# ArticulatedPCBEndLED.net
KiCad netlist of a schematic drawn in EAGLE
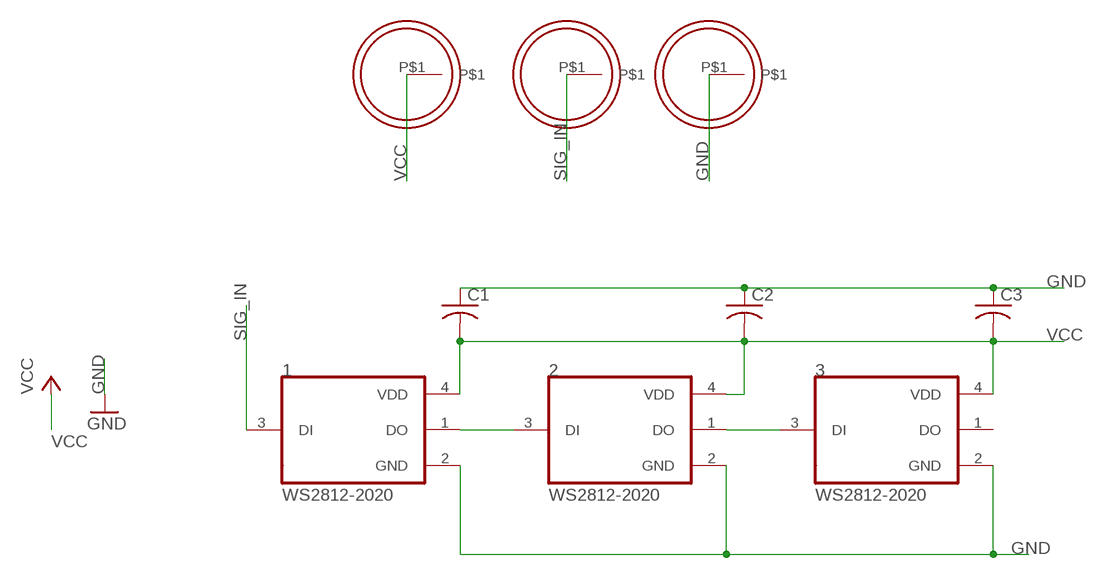
[diagram p0: schematic, sheet 1]

(export (version "E")
  (design (tool "Eeschema 10.0.6"))
  (components
    (comp (ref "1")
      (value "WS2812-2020")
      (footprint "eagle-import:LED_WS2812-2020")
      (fields (field (name "MF") "Worldsemi"))
      (libsource (lib "eagle-import") (part "WS2812-2020"))
    )
    (comp (ref "2")
      (value "WS2812-2020")
      (footprint "eagle-import:LED_WS2812-2020")
      (fields (field (name "MF") "Worldsemi"))
      (libsource (lib "eagle-import") (part "WS2812-2020"))
    )
    (comp (ref "3")
      (value "WS2812-2020")
      (footprint "eagle-import:LED_WS2812-2020")
      (fields (field (name "MF") "Worldsemi"))
      (libsource (lib "eagle-import") (part "WS2812-2020"))
    )
    (comp (ref "C1")
      (value "C-USC0603")
      (footprint "eagle-import:C0603")
      (libsource (lib "eagle-import") (part "C-USC0603"))
    )
    (comp (ref "C2")
      (value "C-USC0603")
      (footprint "eagle-import:C0603")
      (libsource (lib "eagle-import") (part "C-USC0603"))
    )
    (comp (ref "C3")
      (value "C-USC0603")
      (footprint "eagle-import:C0603")
      (libsource (lib "eagle-import") (part "C-USC0603"))
    )
    (comp (ref "U$2")
      (value "CIRCLE_PAD_17_2_OD")
      (footprint "eagle-import:CIRCLE_PAD_17_2_OD")
      (libsource (lib "eagle-import") (part "CIRCLE_PAD_17_2_OD"))
    )
    (comp (ref "U$3")
      (value "CIRCLE_PAD_8_2_OD")
      (footprint "eagle-import:CIRCLE_PAD_8_2_OD")
      (libsource (lib "eagle-import") (part "CIRCLE_PAD_8_2_OD"))
    )
    (comp (ref "U$4")
      (value "CIRCLE_PAD_12_7_OD")
      (footprint "eagle-import:CIRCLE_PAD_12_7_OD")
      (libsource (lib "eagle-import") (part "CIRCLE_PAD_12_7_OD"))
    )
  )
  (nets
    (net (code "1") (name "/SIG_IN") (class "Default")
      (node (ref "1") (pin "3") (pinfunction "DI_3") (pintype "input"))
      (node (ref "U$4") (pin "P$1") (pinfunction "P$1_P$1") (pintype "bidirectional"))
    )
    (net (code "2") (name "GND") (class "Default")
      (node (ref "1") (pin "2") (pinfunction "GND_2") (pintype "power_in"))
      (node (ref "2") (pin "2") (pinfunction "GND_2") (pintype "power_in"))
      (node (ref "3") (pin "2") (pinfunction "GND_2") (pintype "power_in"))
      (node (ref "C1") (pin "1") (pinfunction "1_1") (pintype "passive"))
      (node (ref "C2") (pin "1") (pinfunction "1_1") (pintype "passive"))
      (node (ref "C3") (pin "1") (pinfunction "1_1") (pintype "passive"))
      (node (ref "U$2") (pin "P$1") (pinfunction "P$1_P$1") (pintype "bidirectional"))
    )
    (net (code "3") (name "Net-(1-DO)") (class "Default")
      (node (ref "1") (pin "1") (pinfunction "DO_1") (pintype "output"))
      (node (ref "2") (pin "3") (pinfunction "DI_3") (pintype "input"))
    )
    (net (code "4") (name "Net-(2-DO)") (class "Default")
      (node (ref "2") (pin "1") (pinfunction "DO_1") (pintype "output"))
      (node (ref "3") (pin "3") (pinfunction "DI_3") (pintype "input"))
    )
    (net (code "5") (name "VCC") (class "Default")
      (node (ref "1") (pin "4") (pinfunction "VDD_4") (pintype "power_in"))
      (node (ref "2") (pin "4") (pinfunction "VDD_4") (pintype "power_in"))
      (node (ref "3") (pin "4") (pinfunction "VDD_4") (pintype "power_in"))
      (node (ref "C1") (pin "2") (pinfunction "2_2") (pintype "passive"))
      (node (ref "C2") (pin "2") (pinfunction "2_2") (pintype "passive"))
      (node (ref "C3") (pin "2") (pinfunction "2_2") (pintype "passive"))
      (node (ref "U$3") (pin "P$1") (pinfunction "P$1_P$1") (pintype "bidirectional"))
    )
    (net (code "6") (name "unconnected-(3-DO-Pad1)") (class "Default")
      (node (ref "3") (pin "1") (pinfunction "DO_1") (pintype "output"))
    )
  )
)
